# CC3000EM.net
KiCad netlist of a schematic drawn in Altium Designer
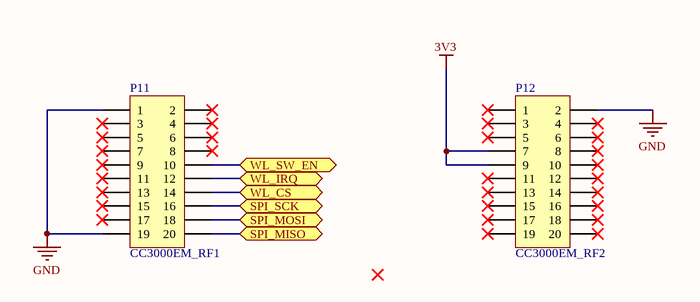
[diagram p0: CC3000EM.SchDoc]

(export (version "E")
  (design (tool "Eeschema 10.0.6"))
  (components
    (comp (ref "P11")
      (value "CC3000EM_RF1")
      (footprint "MHDR2X10")
      (description "Header, 10-Pin, Dual row")
      (libsource (lib "Miscellaneous Connectors") (part "Header 10X2"))
    )
    (comp (ref "P12")
      (value "CC3000EM_RF2")
      (footprint "MHDR2X10")
      (description "Header, 10-Pin, Dual row")
      (libsource (lib "Miscellaneous Connectors") (part "Header 10X2"))
    )
  )
  (nets
    (net (code "1") (name "/SPI_MISO") (class "Default")
      (node (ref "P11") (pin "20") (pinfunction "20_20") (pintype "passive"))
    )
    (net (code "2") (name "/SPI_MOSI") (class "Default")
      (node (ref "P11") (pin "18") (pinfunction "18_18") (pintype "passive"))
    )
    (net (code "3") (name "/SPI_SCK") (class "Default")
      (node (ref "P11") (pin "16") (pinfunction "16_16") (pintype "passive"))
    )
    (net (code "4") (name "/WL_CS") (class "Default")
      (node (ref "P11") (pin "14") (pinfunction "14_14") (pintype "passive"))
    )
    (net (code "5") (name "/WL_IRQ") (class "Default")
      (node (ref "P11") (pin "12") (pinfunction "12_12") (pintype "passive"))
    )
    (net (code "6") (name "/WL_SW_EN") (class "Default")
      (node (ref "P11") (pin "10") (pinfunction "10_10") (pintype "passive"))
    )
    (net (code "7") (name "3V3") (class "Default")
      (node (ref "P12") (pin "7") (pinfunction "7_7") (pintype "passive"))
      (node (ref "P12") (pin "9") (pinfunction "9_9") (pintype "passive"))
    )
    (net (code "8") (name "GND") (class "Default")
      (node (ref "P11") (pin "1") (pinfunction "1_1") (pintype "passive"))
      (node (ref "P11") (pin "19") (pinfunction "19_19") (pintype "passive"))
      (node (ref "P12") (pin "2") (pinfunction "2_2") (pintype "passive"))
    )
    (net (code "9") (name "unconnected-(P11-Pad2)") (class "Default")
      (node (ref "P11") (pin "2") (pinfunction "2_2") (pintype "passive+no_connect"))
    )
    (net (code "10") (name "unconnected-(P11-Pad3)") (class "Default")
      (node (ref "P11") (pin "3") (pinfunction "3_3") (pintype "passive+no_connect"))
    )
    (net (code "11") (name "unconnected-(P11-Pad4)") (class "Default")
      (node (ref "P11") (pin "4") (pinfunction "4_4") (pintype "passive+no_connect"))
    )
    (net (code "12") (name "unconnected-(P11-Pad5)") (class "Default")
      (node (ref "P11") (pin "5") (pinfunction "5_5") (pintype "passive+no_connect"))
    )
    (net (code "13") (name "unconnected-(P11-Pad6)") (class "Default")
      (node (ref "P11") (pin "6") (pinfunction "6_6") (pintype "passive+no_connect"))
    )
    (net (code "14") (name "unconnected-(P11-Pad7)") (class "Default")
      (node (ref "P11") (pin "7") (pinfunction "7_7") (pintype "passive+no_connect"))
    )
    (net (code "15") (name "unconnected-(P11-Pad8)") (class "Default")
      (node (ref "P11") (pin "8") (pinfunction "8_8") (pintype "passive+no_connect"))
    )
    (net (code "16") (name "unconnected-(P11-Pad9)") (class "Default")
      (node (ref "P11") (pin "9") (pinfunction "9_9") (pintype "passive+no_connect"))
    )
    (net (code "17") (name "unconnected-(P11-Pad11)") (class "Default")
      (node (ref "P11") (pin "11") (pinfunction "11_11") (pintype "passive+no_connect"))
    )
    (net (code "18") (name "unconnected-(P11-Pad13)") (class "Default")
      (node (ref "P11") (pin "13") (pinfunction "13_13") (pintype "passive+no_connect"))
    )
    (net (code "19") (name "unconnected-(P11-Pad15)") (class "Default")
      (node (ref "P11") (pin "15") (pinfunction "15_15") (pintype "passive+no_connect"))
    )
    (net (code "20") (name "unconnected-(P11-Pad17)") (class "Default")
      (node (ref "P11") (pin "17") (pinfunction "17_17") (pintype "passive+no_connect"))
    )
    (net (code "21") (name "unconnected-(P12-Pad1)") (class "Default")
      (node (ref "P12") (pin "1") (pinfunction "1_1") (pintype "passive+no_connect"))
    )
    (net (code "22") (name "unconnected-(P12-Pad3)") (class "Default")
      (node (ref "P12") (pin "3") (pinfunction "3_3") (pintype "passive+no_connect"))
    )
    (net (code "23") (name "unconnected-(P12-Pad4)") (class "Default")
      (node (ref "P12") (pin "4") (pinfunction "4_4") (pintype "passive+no_connect"))
    )
    (net (code "24") (name "unconnected-(P12-Pad5)") (class "Default")
      (node (ref "P12") (pin "5") (pinfunction "5_5") (pintype "passive+no_connect"))
    )
    (net (code "25") (name "unconnected-(P12-Pad6)") (class "Default")
      (node (ref "P12") (pin "6") (pinfunction "6_6") (pintype "passive+no_connect"))
    )
    (net (code "26") (name "unconnected-(P12-Pad8)") (class "Default")
      (node (ref "P12") (pin "8") (pinfunction "8_8") (pintype "passive+no_connect"))
    )
    (net (code "27") (name "unconnected-(P12-Pad10)") (class "Default")
      (node (ref "P12") (pin "10") (pinfunction "10_10") (pintype "passive+no_connect"))
    )
    (net (code "28") (name "unconnected-(P12-Pad11)") (class "Default")
      (node (ref "P12") (pin "11") (pinfunction "11_11") (pintype "passive+no_connect"))
    )
    (net (code "29") (name "unconnected-(P12-Pad12)") (class "Default")
      (node (ref "P12") (pin "12") (pinfunction "12_12") (pintype "passive+no_connect"))
    )
    (net (code "30") (name "unconnected-(P12-Pad13)") (class "Default")
      (node (ref "P12") (pin "13") (pinfunction "13_13") (pintype "passive+no_connect"))
    )
    (net (code "31") (name "unconnected-(P12-Pad14)") (class "Default")
      (node (ref "P12") (pin "14") (pinfunction "14_14") (pintype "passive+no_connect"))
    )
    (net (code "32") (name "unconnected-(P12-Pad15)") (class "Default")
      (node (ref "P12") (pin "15") (pinfunction "15_15") (pintype "passive+no_connect"))
    )
    (net (code "33") (name "unconnected-(P12-Pad16)") (class "Default")
      (node (ref "P12") (pin "16") (pinfunction "16_16") (pintype "passive+no_connect"))
    )
    (net (code "34") (name "unconnected-(P12-Pad17)") (class "Default")
      (node (ref "P12") (pin "17") (pinfunction "17_17") (pintype "passive+no_connect"))
    )
    (net (code "35") (name "unconnected-(P12-Pad18)") (class "Default")
      (node (ref "P12") (pin "18") (pinfunction "18_18") (pintype "passive+no_connect"))
    )
    (net (code "36") (name "unconnected-(P12-Pad19)") (class "Default")
      (node (ref "P12") (pin "19") (pinfunction "19_19") (pintype "passive+no_connect"))
    )
    (net (code "37") (name "unconnected-(P12-Pad20)") (class "Default")
      (node (ref "P12") (pin "20") (pinfunction "20_20") (pintype "passive+no_connect"))
    )
  )
)
